# sensorstation_ok_pwr.net
KiCad netlist of a schematic drawn in EAGLE
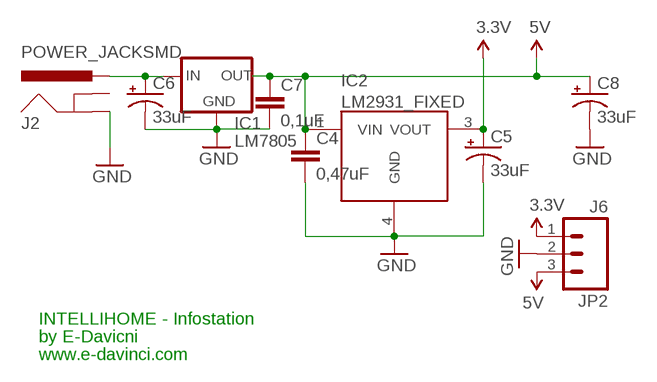
[diagram p0: schematic, sheet 1]

(export (version "E")
  (design (tool "Eeschema 10.0.6"))
  (components
    (comp (ref "C4")
      (value "0,47uF")
      (footprint "eagle-import:CAP-PTH-SMALL-KIT")
      (libsource (lib "eagle-import") (part "CAPKIT"))
    )
    (comp (ref "C5")
      (value "33uF")
      (footprint "eagle-import:CPOL-RADIAL-10UF-25V")
      (libsource (lib "eagle-import") (part "CAP_POLPTH2"))
    )
    (comp (ref "C6")
      (value "33uF")
      (footprint "eagle-import:CPOL-RADIAL-10UF-25V")
      (libsource (lib "eagle-import") (part "CAP_POLPTH2"))
    )
    (comp (ref "C7")
      (value "0,1uF")
      (footprint "eagle-import:CAP-PTH-SMALL-KIT")
      (libsource (lib "eagle-import") (part "CAPKIT"))
    )
    (comp (ref "C8")
      (value "33uF")
      (footprint "eagle-import:CPOL-RADIAL-10UF-25V")
      (libsource (lib "eagle-import") (part "CAP_POLPTH2"))
    )
    (comp (ref "IC1")
      (value "LM7805")
      (footprint "eagle-import:TO-220-ALT")
      (libsource (lib "eagle-import") (part "V_REG_78XX-TO-220"))
    )
    (comp (ref "IC2")
      (value "LM2931_FIXED")
      (footprint "eagle-import:DPAK")
      (libsource (lib "eagle-import") (part "LM2931_FIXED"))
    )
    (comp (ref "J2")
      (value "POWER_JACKSMD")
      (footprint "eagle-import:POWER_JACK_SMD")
      (libsource (lib "eagle-import") (part "POWER_JACKSMD"))
    )
    (comp (ref "JP2")
      (value "J6")
      (footprint "eagle-import:1X03")
      (libsource (lib "eagle-import") (part "M03PTH"))
    )
  )
  (nets
    (net (code "1") (name "3.3V") (class "Default")
      (node (ref "C5") (pin "1") (pinfunction "+_1") (pintype "passive"))
      (node (ref "IC2") (pin "3") (pinfunction "VOUT_3") (pintype "bidirectional"))
      (node (ref "JP2") (pin "1") (pinfunction "1_1") (pintype "passive"))
    )
    (net (code "2") (name "5V") (class "Default")
      (node (ref "C4") (pin "1") (pinfunction "1_1") (pintype "passive"))
      (node (ref "C7") (pin "1") (pinfunction "1_1") (pintype "passive"))
      (node (ref "C8") (pin "1") (pinfunction "+_1") (pintype "passive"))
      (node (ref "IC1") (pin "OUT") (pinfunction "OUT_OUT") (pintype "output"))
      (node (ref "IC2") (pin "1") (pinfunction "VIN_1") (pintype "bidirectional"))
      (node (ref "JP2") (pin "3") (pinfunction "3_3") (pintype "passive"))
    )
    (net (code "3") (name "GND") (class "Default")
      (node (ref "C4") (pin "2") (pinfunction "2_2") (pintype "passive"))
      (node (ref "C5") (pin "2") (pinfunction "-_2") (pintype "passive"))
      (node (ref "C6") (pin "2") (pinfunction "-_2") (pintype "passive"))
      (node (ref "C7") (pin "2") (pinfunction "2_2") (pintype "passive"))
      (node (ref "C8") (pin "2") (pinfunction "-_2") (pintype "passive"))
      (node (ref "IC1") (pin "GND") (pinfunction "GND_GND") (pintype "input"))
      (node (ref "IC2") (pin "4") (pinfunction "GND_4") (pintype "bidirectional"))
      (node (ref "J2") (pin "P$4") (pinfunction "GND_P$4") (pintype "bidirectional"))
      (node (ref "JP2") (pin "2") (pinfunction "2_2") (pintype "passive"))
    )
    (net (code "4") (name "Net-(C6-+)") (class "Default")
      (node (ref "C6") (pin "1") (pinfunction "+_1") (pintype "passive"))
      (node (ref "IC1") (pin "IN") (pinfunction "IN_IN") (pintype "input"))
      (node (ref "J2") (pin "VIN0") (pinfunction "PWR_VIN0") (pintype "bidirectional"))
    )
    (net (code "5") (name "unconnected-(J2-GNDBREAK-PadGND)") (class "Default")
      (node (ref "J2") (pin "GND") (pinfunction "GNDBREAK_GND") (pintype "bidirectional"))
    )
  )
)
